# Sheet1.net
KiCad netlist of a schematic drawn in Altium Designer
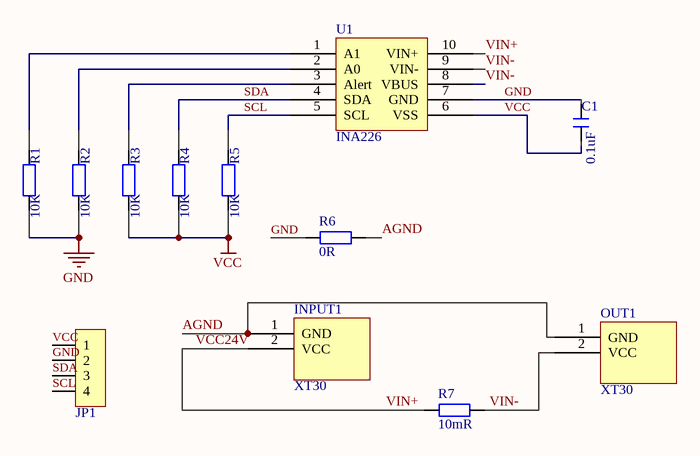
[diagram p0: Sheet1.SchDoc]

(export (version "E")
  (design (tool "Eeschema 10.0.6"))
  (components
    (comp (ref "C1")
      (value "0.1uF")
      (footprint "C 0603_L")
      (description "贴片电容")
      (libsource (lib "0.1 - 电阻-电容-电感") (part "C"))
    )
    (comp (ref "INPUT1") (value "XT30") (footprint "XT30") (libsource (lib "PCB_Project") (part "XT30")))
    (comp (ref "JP1")
      (value "HDR-1X4")
      (footprint "XH2.54-WI-4P")
      (description "4P接插件")
      (fields (field (name "版权归属") "封装库来自淘宝 ID：黄晶宝石"))
      (libsource (lib "5.3 - 接插件-脚距2.54 (100mil) ") (part "Header 4"))
    )
    (comp (ref "OUT1") (value "XT30") (footprint "XT30") (libsource (lib "PCB_Project") (part "XT30")))
    (comp (ref "R1")
      (value "10K")
      (footprint "R 0603_L")
      (description "贴片电阻")
      (fields (field (name "版权归属") "来自淘宝 ID：黄晶宝石"))
      (libsource (lib "0.1 - 电阻-电容-电感") (part "R"))
    )
    (comp (ref "R2")
      (value "10K")
      (footprint "R 0603_L")
      (description "贴片电阻")
      (fields (field (name "版权归属") "来自淘宝 ID：黄晶宝石"))
      (libsource (lib "0.1 - 电阻-电容-电感") (part "R"))
    )
    (comp (ref "R3")
      (value "10K")
      (footprint "R 0603_L")
      (description "贴片电阻")
      (fields (field (name "版权归属") "来自淘宝 ID：黄晶宝石"))
      (libsource (lib "0.1 - 电阻-电容-电感") (part "R"))
    )
    (comp (ref "R4")
      (value "10K")
      (footprint "R 0603_L")
      (description "贴片电阻")
      (fields (field (name "版权归属") "来自淘宝 ID：黄晶宝石"))
      (libsource (lib "0.1 - 电阻-电容-电感") (part "R"))
    )
    (comp (ref "R5")
      (value "10K")
      (footprint "R 0603_L")
      (description "贴片电阻")
      (fields (field (name "版权归属") "来自淘宝 ID：黄晶宝石"))
      (libsource (lib "0.1 - 电阻-电容-电感") (part "R"))
    )
    (comp (ref "R6")
      (value "0R")
      (footprint "R 0805_L")
      (description "贴片电阻")
      (fields (field (name "版权归属") "来自淘宝 ID：黄晶宝石"))
      (libsource (lib "0.1 - 电阻-电容-电感") (part "R"))
    )
    (comp (ref "R7")
      (value "10mR")
      (footprint "R 2512_L")
      (description "贴片电阻")
      (fields (field (name "版权归属") "来自淘宝 ID：黄晶宝石"))
      (libsource (lib "0.1 - 电阻-电容-电感") (part "R"))
    )
    (comp (ref "U1") (value "INA226") (footprint "MSOP-10") (libsource (lib "Schlib1") (part "ina226")))
  )
  (nets
    (net (code "1") (name "/AGND") (class "Default")
      (node (ref "INPUT1") (pin "1") (pinfunction "GND_1") (pintype "passive"))
      (node (ref "OUT1") (pin "1") (pinfunction "GND_1") (pintype "passive"))
      (node (ref "R6") (pin "1") (pinfunction "1_1") (pintype "passive"))
    )
    (net (code "2") (name "/SCL") (class "Default")
      (node (ref "JP1") (pin "4") (pinfunction "4_4") (pintype "passive"))
      (node (ref "R5") (pin "2") (pinfunction "2_2") (pintype "passive"))
      (node (ref "U1") (pin "5") (pinfunction "SCL_5") (pintype "passive"))
    )
    (net (code "3") (name "/SDA") (class "Default")
      (node (ref "JP1") (pin "3") (pinfunction "3_3") (pintype "passive"))
      (node (ref "R4") (pin "2") (pinfunction "2_2") (pintype "passive"))
      (node (ref "U1") (pin "4") (pinfunction "SDA_4") (pintype "passive"))
    )
    (net (code "4") (name "/VCC24V") (class "Default")
      (node (ref "INPUT1") (pin "2") (pinfunction "VCC_2") (pintype "passive"))
      (node (ref "R7") (pin "1") (pinfunction "1_1") (pintype "passive"))
      (node (ref "U1") (pin "10") (pinfunction "VIN+_10") (pintype "passive"))
    )
    (net (code "5") (name "/VIN-") (class "Default")
      (node (ref "OUT1") (pin "2") (pinfunction "VCC_2") (pintype "passive"))
      (node (ref "R7") (pin "2") (pinfunction "2_2") (pintype "passive"))
      (node (ref "U1") (pin "8") (pinfunction "VBUS_8") (pintype "passive"))
      (node (ref "U1") (pin "9") (pinfunction "VIN-_9") (pintype "passive"))
    )
    (net (code "6") (name "GND") (class "Default")
      (node (ref "C1") (pin "2") (pinfunction "2_2") (pintype "passive"))
      (node (ref "JP1") (pin "2") (pinfunction "2_2") (pintype "passive"))
      (node (ref "R1") (pin "1") (pinfunction "1_1") (pintype "passive"))
      (node (ref "R2") (pin "1") (pinfunction "1_1") (pintype "passive"))
      (node (ref "R6") (pin "2") (pinfunction "2_2") (pintype "passive"))
      (node (ref "U1") (pin "7") (pinfunction "GND_7") (pintype "passive"))
    )
    (net (code "7") (name "Net-(U1-A0)") (class "Default")
      (node (ref "R2") (pin "2") (pinfunction "2_2") (pintype "passive"))
      (node (ref "U1") (pin "2") (pinfunction "A0_2") (pintype "passive"))
    )
    (net (code "8") (name "Net-(U1-A1)") (class "Default")
      (node (ref "R1") (pin "2") (pinfunction "2_2") (pintype "passive"))
      (node (ref "U1") (pin "1") (pinfunction "A1_1") (pintype "passive"))
    )
    (net (code "9") (name "Net-(U1-Alert)") (class "Default")
      (node (ref "R3") (pin "2") (pinfunction "2_2") (pintype "passive"))
      (node (ref "U1") (pin "3") (pinfunction "Alert_3") (pintype "passive"))
    )
    (net (code "10") (name "VCC") (class "Default")
      (node (ref "C1") (pin "1") (pinfunction "1_1") (pintype "passive"))
      (node (ref "JP1") (pin "1") (pinfunction "1_1") (pintype "passive"))
      (node (ref "R3") (pin "1") (pinfunction "1_1") (pintype "passive"))
      (node (ref "R4") (pin "1") (pinfunction "1_1") (pintype "passive"))
      (node (ref "R5") (pin "1") (pinfunction "1_1") (pintype "passive"))
      (node (ref "U1") (pin "6") (pinfunction "VSS_6") (pintype "passive"))
    )
  )
)
